# shift_register_MOSFET_1.net
KiCad netlist of a schematic drawn in EAGLE
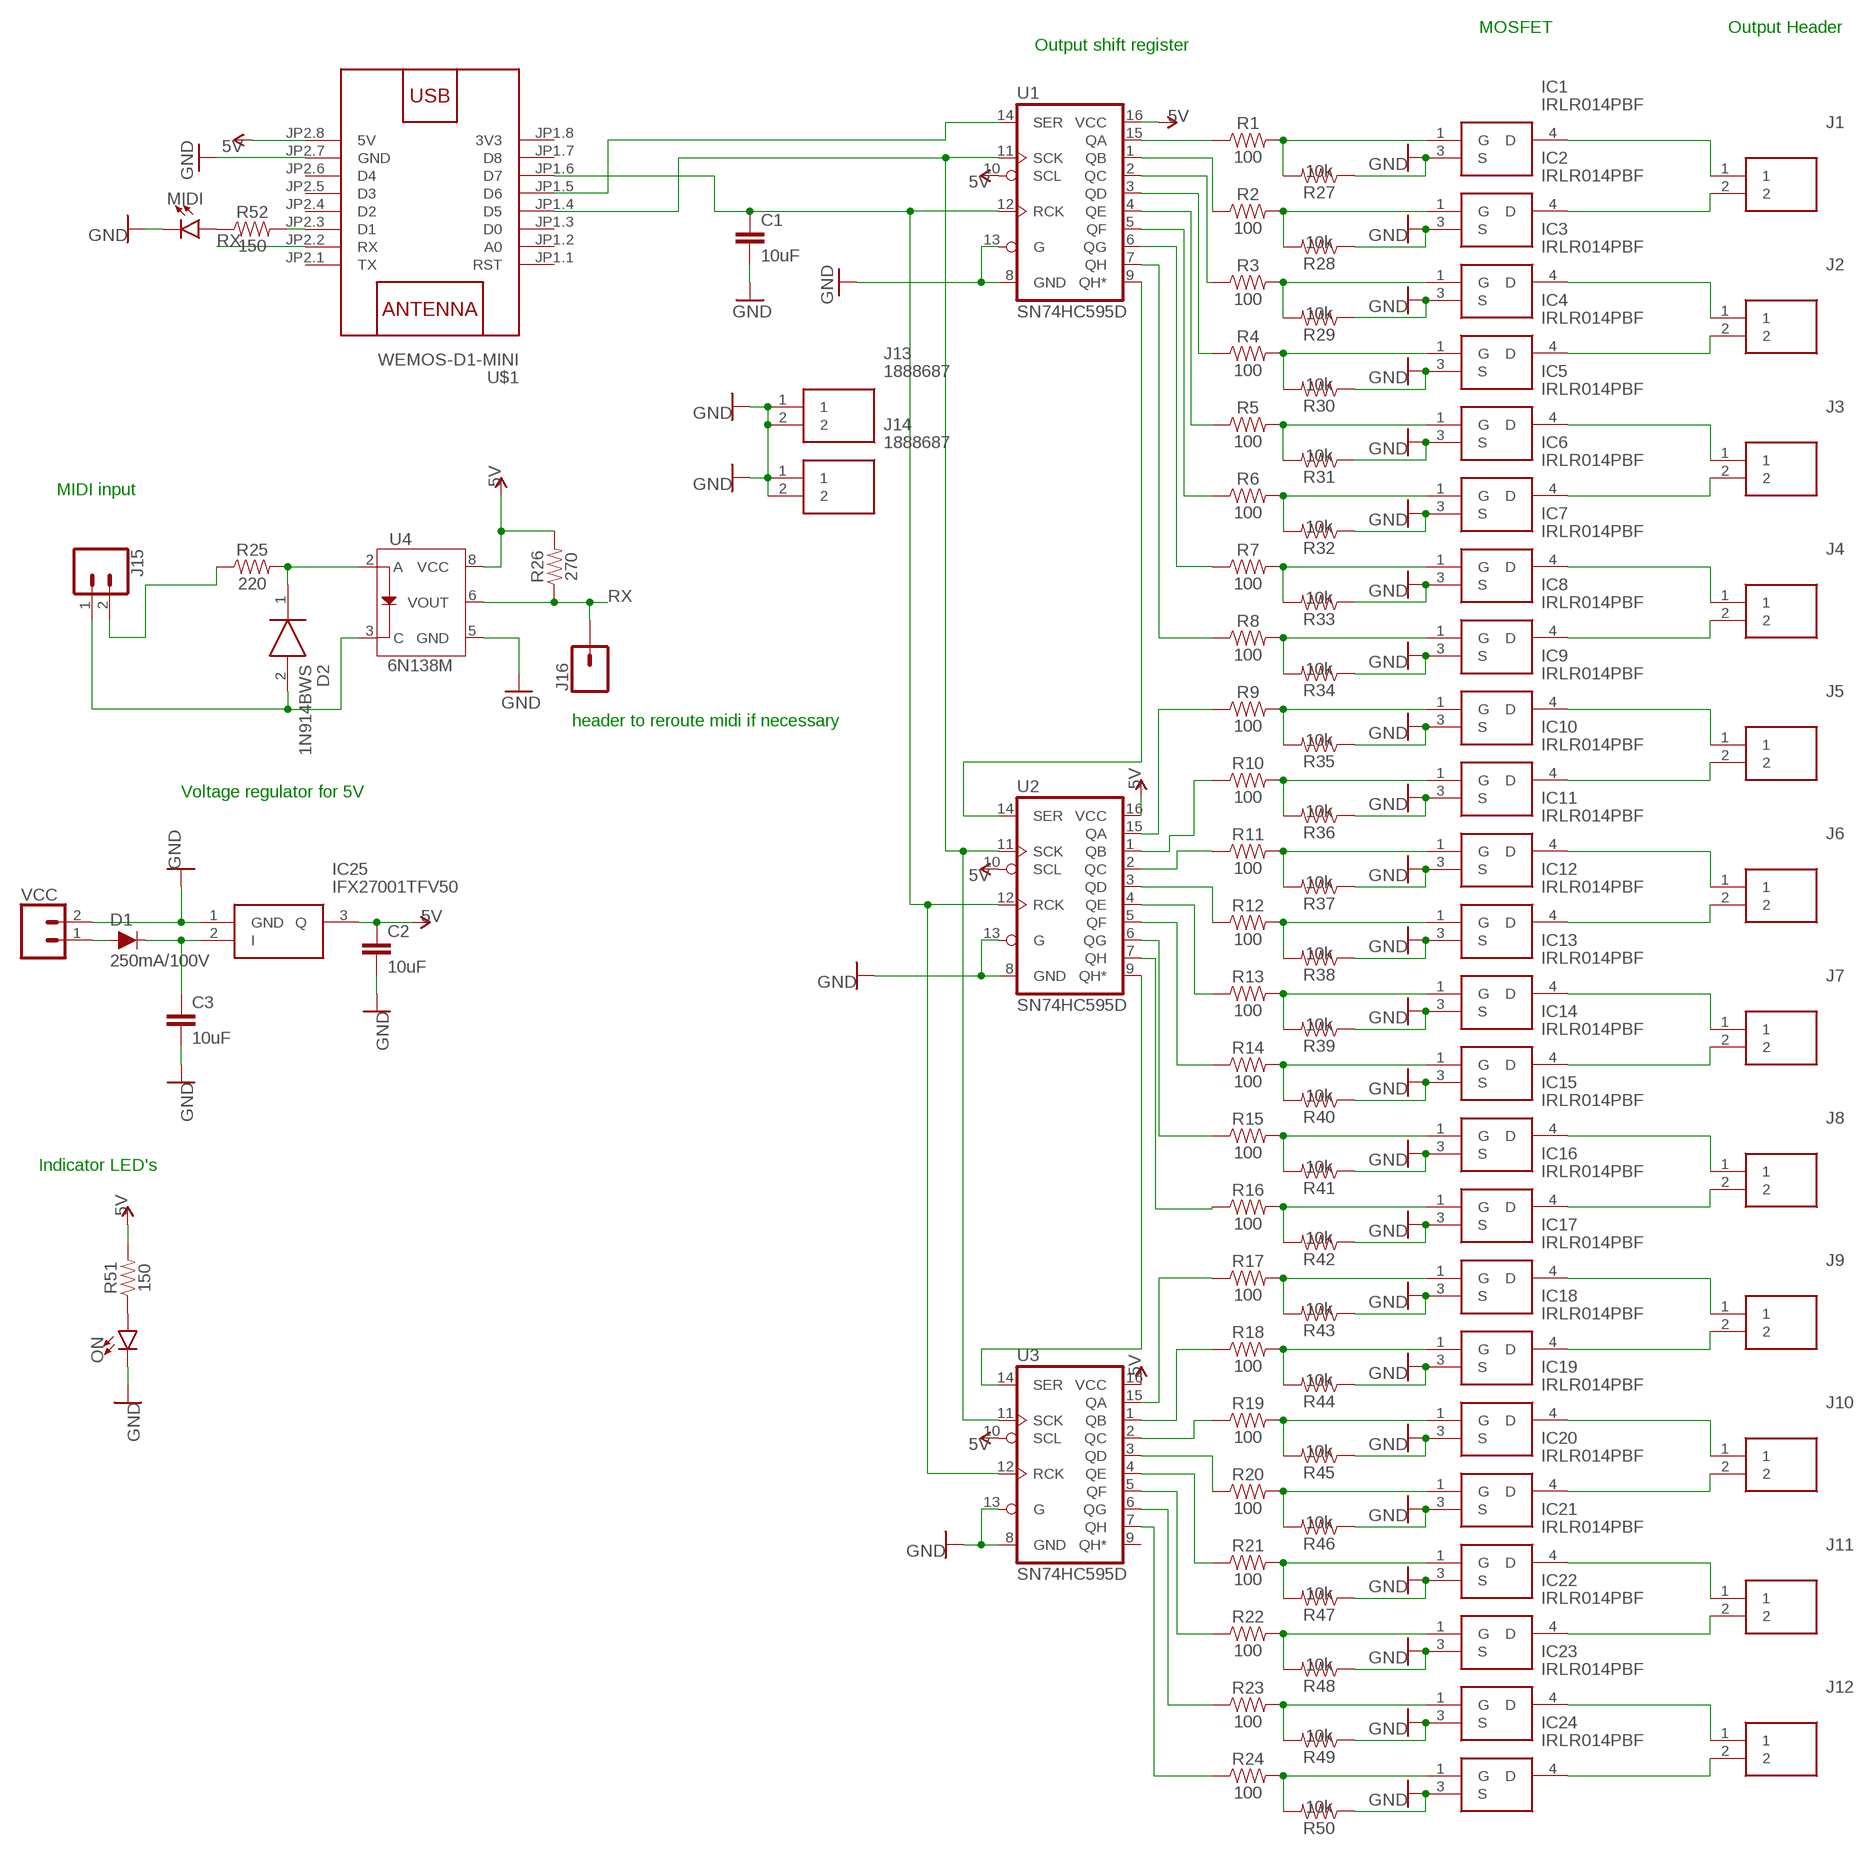
[diagram p0: schematic, sheet 1]

(export (version "E")
  (design (tool "Eeschema 10.0.6"))
  (components
    (comp (ref "C1")
      (value "10uF")
      (footprint "eagle-import:C0805")
      (libsource (lib "eagle-import") (part "C-EUC0805"))
    )
    (comp (ref "C2")
      (value "10uF")
      (footprint "eagle-import:C0805")
      (libsource (lib "eagle-import") (part "C-EUC0805"))
    )
    (comp (ref "C3")
      (value "10uF")
      (footprint "eagle-import:C0805")
      (libsource (lib "eagle-import") (part "C-EUC0805"))
    )
    (comp (ref "D1")
      (value "250mA/100V")
      (footprint "eagle-import:SOD-323")
      (libsource (lib "eagle-import") (part "DIODE-BAS16J"))
    )
    (comp (ref "D2")
      (value "1N914BWS")
      (footprint "eagle-import:SODFL2513X90N")
      (fields (field (name "MOUSER_PART_NUMBER") "512-1N914BWS") (field (name "RS_PART_NUMBER") "8051021P"))
      (libsource (lib "eagle-import") (part "1N914BWS"))
    )
    (comp (ref "IC1")
      (value "IRLR014PBF")
      (footprint "eagle-import:TO228P990X238-3N")
      (fields (field (name "MOUSER_PART_NUMBER") "844-IRLR014PBF") (field (name "RS_PART_NUMBER") "1780908"))
      (libsource (lib "eagle-import") (part "IRLR014PBF"))
    )
    (comp (ref "IC2")
      (value "IRLR014PBF")
      (footprint "eagle-import:TO228P990X238-3N")
      (fields (field (name "MOUSER_PART_NUMBER") "844-IRLR014PBF") (field (name "RS_PART_NUMBER") "1780908"))
      (libsource (lib "eagle-import") (part "IRLR014PBF"))
    )
    (comp (ref "IC3")
      (value "IRLR014PBF")
      (footprint "eagle-import:TO228P990X238-3N")
      (fields (field (name "MOUSER_PART_NUMBER") "844-IRLR014PBF") (field (name "RS_PART_NUMBER") "1780908"))
      (libsource (lib "eagle-import") (part "IRLR014PBF"))
    )
    (comp (ref "IC4")
      (value "IRLR014PBF")
      (footprint "eagle-import:TO228P990X238-3N")
      (fields (field (name "MOUSER_PART_NUMBER") "844-IRLR014PBF") (field (name "RS_PART_NUMBER") "1780908"))
      (libsource (lib "eagle-import") (part "IRLR014PBF"))
    )
    (comp (ref "IC5")
      (value "IRLR014PBF")
      (footprint "eagle-import:TO228P990X238-3N")
      (fields (field (name "MOUSER_PART_NUMBER") "844-IRLR014PBF") (field (name "RS_PART_NUMBER") "1780908"))
      (libsource (lib "eagle-import") (part "IRLR014PBF"))
    )
    (comp (ref "IC6")
      (value "IRLR014PBF")
      (footprint "eagle-import:TO228P990X238-3N")
      (fields (field (name "MOUSER_PART_NUMBER") "844-IRLR014PBF") (field (name "RS_PART_NUMBER") "1780908"))
      (libsource (lib "eagle-import") (part "IRLR014PBF"))
    )
    (comp (ref "IC7")
      (value "IRLR014PBF")
      (footprint "eagle-import:TO228P990X238-3N")
      (fields (field (name "MOUSER_PART_NUMBER") "844-IRLR014PBF") (field (name "RS_PART_NUMBER") "1780908"))
      (libsource (lib "eagle-import") (part "IRLR014PBF"))
    )
    (comp (ref "IC8")
      (value "IRLR014PBF")
      (footprint "eagle-import:TO228P990X238-3N")
      (fields (field (name "MOUSER_PART_NUMBER") "844-IRLR014PBF") (field (name "RS_PART_NUMBER") "1780908"))
      (libsource (lib "eagle-import") (part "IRLR014PBF"))
    )
    (comp (ref "IC9")
      (value "IRLR014PBF")
      (footprint "eagle-import:TO228P990X238-3N")
      (fields (field (name "MOUSER_PART_NUMBER") "844-IRLR014PBF") (field (name "RS_PART_NUMBER") "1780908"))
      (libsource (lib "eagle-import") (part "IRLR014PBF"))
    )
    (comp (ref "IC10")
      (value "IRLR014PBF")
      (footprint "eagle-import:TO228P990X238-3N")
      (fields (field (name "MOUSER_PART_NUMBER") "844-IRLR014PBF") (field (name "RS_PART_NUMBER") "1780908"))
      (libsource (lib "eagle-import") (part "IRLR014PBF"))
    )
    (comp (ref "IC11")
      (value "IRLR014PBF")
      (footprint "eagle-import:TO228P990X238-3N")
      (fields (field (name "MOUSER_PART_NUMBER") "844-IRLR014PBF") (field (name "RS_PART_NUMBER") "1780908"))
      (libsource (lib "eagle-import") (part "IRLR014PBF"))
    )
    (comp (ref "IC12")
      (value "IRLR014PBF")
      (footprint "eagle-import:TO228P990X238-3N")
      (fields (field (name "MOUSER_PART_NUMBER") "844-IRLR014PBF") (field (name "RS_PART_NUMBER") "1780908"))
      (libsource (lib "eagle-import") (part "IRLR014PBF"))
    )
    (comp (ref "IC13")
      (value "IRLR014PBF")
      (footprint "eagle-import:TO228P990X238-3N")
      (fields (field (name "MOUSER_PART_NUMBER") "844-IRLR014PBF") (field (name "RS_PART_NUMBER") "1780908"))
      (libsource (lib "eagle-import") (part "IRLR014PBF"))
    )
    (comp (ref "IC14")
      (value "IRLR014PBF")
      (footprint "eagle-import:TO228P990X238-3N")
      (fields (field (name "MOUSER_PART_NUMBER") "844-IRLR014PBF") (field (name "RS_PART_NUMBER") "1780908"))
      (libsource (lib "eagle-import") (part "IRLR014PBF"))
    )
    (comp (ref "IC15")
      (value "IRLR014PBF")
      (footprint "eagle-import:TO228P990X238-3N")
      (fields (field (name "MOUSER_PART_NUMBER") "844-IRLR014PBF") (field (name "RS_PART_NUMBER") "1780908"))
      (libsource (lib "eagle-import") (part "IRLR014PBF"))
    )
    (comp (ref "IC16")
      (value "IRLR014PBF")
      (footprint "eagle-import:TO228P990X238-3N")
      (fields (field (name "MOUSER_PART_NUMBER") "844-IRLR014PBF") (field (name "RS_PART_NUMBER") "1780908"))
      (libsource (lib "eagle-import") (part "IRLR014PBF"))
    )
    (comp (ref "IC17")
      (value "IRLR014PBF")
      (footprint "eagle-import:TO228P990X238-3N")
      (fields (field (name "MOUSER_PART_NUMBER") "844-IRLR014PBF") (field (name "RS_PART_NUMBER") "1780908"))
      (libsource (lib "eagle-import") (part "IRLR014PBF"))
    )
    (comp (ref "IC18")
      (value "IRLR014PBF")
      (footprint "eagle-import:TO228P990X238-3N")
      (fields (field (name "MOUSER_PART_NUMBER") "844-IRLR014PBF") (field (name "RS_PART_NUMBER") "1780908"))
      (libsource (lib "eagle-import") (part "IRLR014PBF"))
    )
    (comp (ref "IC19")
      (value "IRLR014PBF")
      (footprint "eagle-import:TO228P990X238-3N")
      (fields (field (name "MOUSER_PART_NUMBER") "844-IRLR014PBF") (field (name "RS_PART_NUMBER") "1780908"))
      (libsource (lib "eagle-import") (part "IRLR014PBF"))
    )
    (comp (ref "IC20")
      (value "IRLR014PBF")
      (footprint "eagle-import:TO228P990X238-3N")
      (fields (field (name "MOUSER_PART_NUMBER") "844-IRLR014PBF") (field (name "RS_PART_NUMBER") "1780908"))
      (libsource (lib "eagle-import") (part "IRLR014PBF"))
    )
    (comp (ref "IC21")
      (value "IRLR014PBF")
      (footprint "eagle-import:TO228P990X238-3N")
      (fields (field (name "MOUSER_PART_NUMBER") "844-IRLR014PBF") (field (name "RS_PART_NUMBER") "1780908"))
      (libsource (lib "eagle-import") (part "IRLR014PBF"))
    )
    (comp (ref "IC22")
      (value "IRLR014PBF")
      (footprint "eagle-import:TO228P990X238-3N")
      (fields (field (name "MOUSER_PART_NUMBER") "844-IRLR014PBF") (field (name "RS_PART_NUMBER") "1780908"))
      (libsource (lib "eagle-import") (part "IRLR014PBF"))
    )
    (comp (ref "IC23")
      (value "IRLR014PBF")
      (footprint "eagle-import:TO228P990X238-3N")
      (fields (field (name "MOUSER_PART_NUMBER") "844-IRLR014PBF") (field (name "RS_PART_NUMBER") "1780908"))
      (libsource (lib "eagle-import") (part "IRLR014PBF"))
    )
    (comp (ref "IC24")
      (value "IRLR014PBF")
      (footprint "eagle-import:TO228P990X238-3N")
      (fields (field (name "MOUSER_PART_NUMBER") "844-IRLR014PBF") (field (name "RS_PART_NUMBER") "1780908"))
      (libsource (lib "eagle-import") (part "IRLR014PBF"))
    )
    (comp (ref "IC25")
      (value "IFX27001TFV50")
      (footprint "eagle-import:PG-TO252-3-11")
      (fields (field (name "RS_PART_NUMBER") "1459664"))
      (libsource (lib "eagle-import") (part "IFX27001TFV50"))
    )
    (comp (ref "J1")
      (value "1888687")
      (footprint "eagle-import:SHDR2W90P0X508_1X2_1016X950X15")
      (fields (field (name "MOUSER_PART_NUMBER") "651-1888687") (field (name "RS_PART_NUMBER") "2509972333"))
      (libsource (lib "eagle-import") (part "1888687"))
    )
    (comp (ref "J2")
      (value "1888687")
      (footprint "eagle-import:SHDR2W90P0X508_1X2_1016X950X15")
      (fields (field (name "MOUSER_PART_NUMBER") "651-1888687") (field (name "RS_PART_NUMBER") "2509972333"))
      (libsource (lib "eagle-import") (part "1888687"))
    )
    (comp (ref "J3")
      (value "1888687")
      (footprint "eagle-import:SHDR2W90P0X508_1X2_1016X950X15")
      (fields (field (name "MOUSER_PART_NUMBER") "651-1888687") (field (name "RS_PART_NUMBER") "2509972333"))
      (libsource (lib "eagle-import") (part "1888687"))
    )
    (comp (ref "J4")
      (value "1888687")
      (footprint "eagle-import:SHDR2W90P0X508_1X2_1016X950X15")
      (fields (field (name "MOUSER_PART_NUMBER") "651-1888687") (field (name "RS_PART_NUMBER") "2509972333"))
      (libsource (lib "eagle-import") (part "1888687"))
    )
    (comp (ref "J5")
      (value "1888687")
      (footprint "eagle-import:SHDR2W90P0X508_1X2_1016X950X15")
      (fields (field (name "MOUSER_PART_NUMBER") "651-1888687") (field (name "RS_PART_NUMBER") "2509972333"))
      (libsource (lib "eagle-import") (part "1888687"))
    )
    (comp (ref "J6")
      (value "1888687")
      (footprint "eagle-import:SHDR2W90P0X508_1X2_1016X950X15")
      (fields (field (name "MOUSER_PART_NUMBER") "651-1888687") (field (name "RS_PART_NUMBER") "2509972333"))
      (libsource (lib "eagle-import") (part "1888687"))
    )
    (comp (ref "J7")
      (value "1888687")
      (footprint "eagle-import:SHDR2W90P0X508_1X2_1016X950X15")
      (fields (field (name "MOUSER_PART_NUMBER") "651-1888687") (field (name "RS_PART_NUMBER") "2509972333"))
      (libsource (lib "eagle-import") (part "1888687"))
    )
    (comp (ref "J8")
      (value "1888687")
      (footprint "eagle-import:SHDR2W90P0X508_1X2_1016X950X15")
      (fields (field (name "MOUSER_PART_NUMBER") "651-1888687") (field (name "RS_PART_NUMBER") "2509972333"))
      (libsource (lib "eagle-import") (part "1888687"))
    )
    (comp (ref "J9")
      (value "1888687")
      (footprint "eagle-import:SHDR2W90P0X508_1X2_1016X950X15")
      (fields (field (name "MOUSER_PART_NUMBER") "651-1888687") (field (name "RS_PART_NUMBER") "2509972333"))
      (libsource (lib "eagle-import") (part "1888687"))
    )
    (comp (ref "J10")
      (value "1888687")
      (footprint "eagle-import:SHDR2W90P0X508_1X2_1016X950X15")
      (fields (field (name "MOUSER_PART_NUMBER") "651-1888687") (field (name "RS_PART_NUMBER") "2509972333"))
      (libsource (lib "eagle-import") (part "1888687"))
    )
    (comp (ref "J11")
      (value "1888687")
      (footprint "eagle-import:SHDR2W90P0X508_1X2_1016X950X15")
      (fields (field (name "MOUSER_PART_NUMBER") "651-1888687") (field (name "RS_PART_NUMBER") "2509972333"))
      (libsource (lib "eagle-import") (part "1888687"))
    )
    (comp (ref "J12")
      (value "1888687")
      (footprint "eagle-import:SHDR2W90P0X508_1X2_1016X950X15")
      (fields (field (name "MOUSER_PART_NUMBER") "651-1888687") (field (name "RS_PART_NUMBER") "2509972333"))
      (libsource (lib "eagle-import") (part "1888687"))
    )
    (comp (ref "J13")
      (value "1888687")
      (footprint "eagle-import:SHDR2W90P0X508_1X2_1016X950X15")
      (fields (field (name "MOUSER_PART_NUMBER") "651-1888687") (field (name "RS_PART_NUMBER") "2509972333"))
      (libsource (lib "eagle-import") (part "1888687"))
    )
    (comp (ref "J14")
      (value "1888687")
      (footprint "eagle-import:SHDR2W90P0X508_1X2_1016X950X15")
      (fields (field (name "MOUSER_PART_NUMBER") "651-1888687") (field (name "RS_PART_NUMBER") "2509972333"))
      (libsource (lib "eagle-import") (part "1888687"))
    )
    (comp (ref "J15")
      (value "CONN_02")
      (footprint "eagle-import:1X02")
      (libsource (lib "eagle-import") (part "CONN_02"))
    )
    (comp (ref "J16")
      (value "CONN_01")
      (footprint "eagle-import:1X01")
      (libsource (lib "eagle-import") (part "CONN_01"))
    )
    (comp (ref "MIDI")
      (value "LED3MM")
      (footprint "eagle-import:LED_3MM")
      (libsource (lib "eagle-import") (part "LED3MM"))
    )
    (comp (ref "ON")
      (value "LED3MM")
      (footprint "eagle-import:LED_3MM")
      (libsource (lib "eagle-import") (part "LED3MM"))
    )
    (comp (ref "R1")
      (value "100")
      (footprint "eagle-import:0805")
      (libsource (lib "eagle-import") (part "RESISTOR0805"))
    )
    (comp (ref "R2")
      (value "100")
      (footprint "eagle-import:0805")
      (libsource (lib "eagle-import") (part "RESISTOR0805"))
    )
    (comp (ref "R3")
      (value "100")
      (footprint "eagle-import:0805")
      (libsource (lib "eagle-import") (part "RESISTOR0805"))
    )
    (comp (ref "R4")
      (value "100")
      (footprint "eagle-import:0805")
      (libsource (lib "eagle-import") (part "RESISTOR0805"))
    )
    (comp (ref "R5")
      (value "100")
      (footprint "eagle-import:0805")
      (libsource (lib "eagle-import") (part "RESISTOR0805"))
    )
    (comp (ref "R6")
      (value "100")
      (footprint "eagle-import:0805")
      (libsource (lib "eagle-import") (part "RESISTOR0805"))
    )
    (comp (ref "R7")
      (value "100")
      (footprint "eagle-import:0805")
      (libsource (lib "eagle-import") (part "RESISTOR0805"))
    )
    (comp (ref "R8")
      (value "100")
      (footprint "eagle-import:0805")
      (libsource (lib "eagle-import") (part "RESISTOR0805"))
    )
    (comp (ref "R9")
      (value "100")
      (footprint "eagle-import:0805")
      (libsource (lib "eagle-import") (part "RESISTOR0805"))
    )
    (comp (ref "R10")
      (value "100")
      (footprint "eagle-import:0805")
      (libsource (lib "eagle-import") (part "RESISTOR0805"))
    )
    (comp (ref "R11")
      (value "100")
      (footprint "eagle-import:0805")
      (libsource (lib "eagle-import") (part "RESISTOR0805"))
    )
    (comp (ref "R12")
      (value "100")
      (footprint "eagle-import:0805")
      (libsource (lib "eagle-import") (part "RESISTOR0805"))
    )
    (comp (ref "R13")
      (value "100")
      (footprint "eagle-import:0805")
      (libsource (lib "eagle-import") (part "RESISTOR0805"))
    )
    (comp (ref "R14")
      (value "100")
      (footprint "eagle-import:0805")
      (libsource (lib "eagle-import") (part "RESISTOR0805"))
    )
    (comp (ref "R15")
      (value "100")
      (footprint "eagle-import:0805")
      (libsource (lib "eagle-import") (part "RESISTOR0805"))
    )
    (comp (ref "R16")
      (value "100")
      (footprint "eagle-import:0805")
      (libsource (lib "eagle-import") (part "RESISTOR0805"))
    )
    (comp (ref "R17")
      (value "100")
      (footprint "eagle-import:0805")
      (libsource (lib "eagle-import") (part "RESISTOR0805"))
    )
    (comp (ref "R18")
      (value "100")
      (footprint "eagle-import:0805")
      (libsource (lib "eagle-import") (part "RESISTOR0805"))
    )
    (comp (ref "R19")
      (value "100")
      (footprint "eagle-import:0805")
      (libsource (lib "eagle-import") (part "RESISTOR0805"))
    )
    (comp (ref "R20")
      (value "100")
      (footprint "eagle-import:0805")
      (libsource (lib "eagle-import") (part "RESISTOR0805"))
    )
    (comp (ref "R21")
      (value "100")
      (footprint "eagle-import:0805")
      (libsource (lib "eagle-import") (part "RESISTOR0805"))
    )
    (comp (ref "R22")
      (value "100")
      (footprint "eagle-import:0805")
      (libsource (lib "eagle-import") (part "RESISTOR0805"))
    )
    (comp (ref "R23")
      (value "100")
      (footprint "eagle-import:0805")
      (libsource (lib "eagle-import") (part "RESISTOR0805"))
    )
    (comp (ref "R24")
      (value "100")
      (footprint "eagle-import:0805")
      (libsource (lib "eagle-import") (part "RESISTOR0805"))
    )
    (comp (ref "R25")
      (value "220")
      (footprint "eagle-import:0805")
      (libsource (lib "eagle-import") (part "RESISTOR0805"))
    )
    (comp (ref "R26")
      (value "270")
      (footprint "eagle-import:0805")
      (libsource (lib "eagle-import") (part "RESISTOR0805"))
    )
    (comp (ref "R27")
      (value "10k")
      (footprint "eagle-import:0805")
      (libsource (lib "eagle-import") (part "RESISTOR0805"))
    )
    (comp (ref "R28")
      (value "10k")
      (footprint "eagle-import:0805")
      (libsource (lib "eagle-import") (part "RESISTOR0805"))
    )
    (comp (ref "R29")
      (value "10k")
      (footprint "eagle-import:0805")
      (libsource (lib "eagle-import") (part "RESISTOR0805"))
    )
    (comp (ref "R30")
      (value "10k")
      (footprint "eagle-import:0805")
      (libsource (lib "eagle-import") (part "RESISTOR0805"))
    )
    (comp (ref "R31")
      (value "10k")
      (footprint "eagle-import:0805")
      (libsource (lib "eagle-import") (part "RESISTOR0805"))
    )
    (comp (ref "R32")
      (value "10k")
      (footprint "eagle-import:0805")
      (libsource (lib "eagle-import") (part "RESISTOR0805"))
    )
    (comp (ref "R33")
      (value "10k")
      (footprint "eagle-import:0805")
      (libsource (lib "eagle-import") (part "RESISTOR0805"))
    )
    (comp (ref "R34")
      (value "10k")
      (footprint "eagle-import:0805")
      (libsource (lib "eagle-import") (part "RESISTOR0805"))
    )
    (comp (ref "R35")
      (value "10k")
      (footprint "eagle-import:0805")
      (libsource (lib "eagle-import") (part "RESISTOR0805"))
    )
    (comp (ref "R36")
      (value "10k")
      (footprint "eagle-import:0805")
      (libsource (lib "eagle-import") (part "RESISTOR0805"))
    )
    (comp (ref "R37")
      (value "10k")
      (footprint "eagle-import:0805")
      (libsource (lib "eagle-import") (part "RESISTOR0805"))
    )
    (comp (ref "R38")
      (value "10k")
      (footprint "eagle-import:0805")
      (libsource (lib "eagle-import") (part "RESISTOR0805"))
    )
    (comp (ref "R39")
      (value "10k")
      (footprint "eagle-import:0805")
      (libsource (lib "eagle-import") (part "RESISTOR0805"))
    )
    (comp (ref "R40")
      (value "10k")
      (footprint "eagle-import:0805")
      (libsource (lib "eagle-import") (part "RESISTOR0805"))
    )
    (comp (ref "R41")
      (value "10k")
      (footprint "eagle-import:0805")
      (libsource (lib "eagle-import") (part "RESISTOR0805"))
    )
    (comp (ref "R42")
      (value "10k")
      (footprint "eagle-import:0805")
      (libsource (lib "eagle-import") (part "RESISTOR0805"))
    )
    (comp (ref "R43")
      (value "10k")
      (footprint "eagle-import:0805")
      (libsource (lib "eagle-import") (part "RESISTOR0805"))
    )
    (comp (ref "R44")
      (value "10k")
      (footprint "eagle-import:0805")
      (libsource (lib "eagle-import") (part "RESISTOR0805"))
    )
    (comp (ref "R45")
      (value "10k")
      (footprint "eagle-import:0805")
      (libsource (lib "eagle-import") (part "RESISTOR0805"))
    )
    (comp (ref "R46")
      (value "10k")
      (footprint "eagle-import:0805")
      (libsource (lib "eagle-import") (part "RESISTOR0805"))
    )
    (comp (ref "R47")
      (value "10k")
      (footprint "eagle-import:0805")
      (libsource (lib "eagle-import") (part "RESISTOR0805"))
    )
    (comp (ref "R48")
      (value "10k")
      (footprint "eagle-import:0805")
      (libsource (lib "eagle-import") (part "RESISTOR0805"))
    )
    (comp (ref "R49")
      (value "10k")
      (footprint "eagle-import:0805")
      (libsource (lib "eagle-import") (part "RESISTOR0805"))
    )
    (comp (ref "R50")
      (value "10k")
      (footprint "eagle-import:0805")
      (libsource (lib "eagle-import") (part "RESISTOR0805"))
    )
    (comp (ref "R51")
      (value "150")
      (footprint "eagle-import:0805")
      (libsource (lib "eagle-import") (part "RESISTOR0805"))
    )
    (comp (ref "R52")
      (value "150")
      (footprint "eagle-import:0805")
      (libsource (lib "eagle-import") (part "RESISTOR0805"))
    )
    (comp (ref "U$1")
      (value "WEMOS-D1-MINI")
      (footprint "eagle-import:WEMOS-D1-MINI")
      (libsource (lib "eagle-import") (part "WEMOS-D1-MINI"))
    )
    (comp (ref "U1")
      (value "SN74HC595D")
      (footprint "eagle-import:SO16")
      (libsource (lib "eagle-import") (part "74595DHC"))
    )
    (comp (ref "U2")
      (value "SN74HC595D")
      (footprint "eagle-import:SO16")
      (libsource (lib "eagle-import") (part "74595DHC"))
    )
    (comp (ref "U3")
      (value "SN74HC595D")
      (footprint "eagle-import:SO16")
      (libsource (lib "eagle-import") (part "74595DHC"))
    )
    (comp (ref "U4")
      (value "6N138M")
      (footprint "eagle-import:8-SMD")
      (libsource (lib "eagle-import") (part "OPTO_DARL_6N138S"))
    )
    (comp (ref "VCC")
      (value "CONN_02")
      (footprint "eagle-import:1X02")
      (libsource (lib "eagle-import") (part "CONN_02"))
    )
  )
  (nets
    (net (code "1") (name "/3V3") (class "Default")
      (node (ref "U$1") (pin "JP1.8") (pinfunction "3V3_JP1.8") (pintype "power_in"))
    )
    (net (code "2") (name "/RX") (class "Default")
      (node (ref "J16") (pin "1") (pinfunction "1_1") (pintype "passive"))
      (node (ref "R26") (pin "1") (pinfunction "1_1") (pintype "passive"))
      (node (ref "U$1") (pin "JP2.2") (pinfunction "RX_JP2.2") (pintype "bidirectional"))
      (node (ref "U4") (pin "6") (pinfunction "VOUT_6") (pintype "bidirectional"))
    )
    (net (code "3") (name "5V") (class "Default")
      (node (ref "C2") (pin "1") (pinfunction "1_1") (pintype "passive"))
      (node (ref "IC25") (pin "3") (pinfunction "Q_3") (pintype "bidirectional"))
      (node (ref "R26") (pin "2") (pinfunction "2_2") (pintype "passive"))
      (node (ref "R51") (pin "2") (pinfunction "2_2") (pintype "passive"))
      (node (ref "U$1") (pin "JP2.8") (pinfunction "5V_JP2.8") (pintype "power_in"))
      (node (ref "U1") (pin "10") (pinfunction "SCL_10") (pintype "input"))
      (node (ref "U1") (pin "16") (pinfunction "VCC_16") (pintype "power_in"))
      (node (ref "U2") (pin "10") (pinfunction "SCL_10") (pintype "input"))
      (node (ref "U2") (pin "16") (pinfunction "VCC_16") (pintype "power_in"))
      (node (ref "U3") (pin "10") (pinfunction "SCL_10") (pintype "input"))
      (node (ref "U3") (pin "16") (pinfunction "VCC_16") (pintype "power_in"))
      (node (ref "U4") (pin "8") (pinfunction "VCC_8") (pintype "bidirectional"))
    )
    (net (code "4") (name "GND") (class "Default")
      (node (ref "C1") (pin "2") (pinfunction "2_2") (pintype "passive"))
      (node (ref "C2") (pin "2") (pinfunction "2_2") (pintype "passive"))
      (node (ref "C3") (pin "2") (pinfunction "2_2") (pintype "passive"))
      (node (ref "IC1") (pin "3") (pinfunction "S_3") (pintype "bidirectional"))
      (node (ref "IC10") (pin "3") (pinfunction "S_3") (pintype "bidirectional"))
      (node (ref "IC11") (pin "3") (pinfunction "S_3") (pintype "bidirectional"))
      (node (ref "IC12") (pin "3") (pinfunction "S_3") (pintype "bidirectional"))
      (node (ref "IC13") (pin "3") (pinfunction "S_3") (pintype "bidirectional"))
      (node (ref "IC14") (pin "3") (pinfunction "S_3") (pintype "bidirectional"))
      (node (ref "IC15") (pin "3") (pinfunction "S_3") (pintype "bidirectional"))
      (node (ref "IC16") (pin "3") (pinfunction "S_3") (pintype "bidirectional"))
      (node (ref "IC17") (pin "3") (pinfunction "S_3") (pintype "bidirectional"))
      (node (ref "IC18") (pin "3") (pinfunction "S_3") (pintype "bidirectional"))
      (node (ref "IC19") (pin "3") (pinfunction "S_3") (pintype "bidirectional"))
      (node (ref "IC2") (pin "3") (pinfunction "S_3") (pintype "bidirectional"))
      (node (ref "IC20") (pin "3") (pinfunction "S_3") (pintype "bidirectional"))
      (node (ref "IC21") (pin "3") (pinfunction "S_3") (pintype "bidirectional"))
      (node (ref "IC22") (pin "3") (pinfunction "S_3") (pintype "bidirectional"))
      (node (ref "IC23") (pin "3") (pinfunction "S_3") (pintype "bidirectional"))
      (node (ref "IC24") (pin "3") (pinfunction "S_3") (pintype "bidirectional"))
      (node (ref "IC25") (pin "1") (pinfunction "GND_1") (pintype "bidirectional"))
      (node (ref "IC3") (pin "3") (pinfunction "S_3") (pintype "bidirectional"))
      (node (ref "IC4") (pin "3") (pinfunction "S_3") (pintype "bidirectional"))
      (node (ref "IC5") (pin "3") (pinfunction "S_3") (pintype "bidirectional"))
      (node (ref "IC6") (pin "3") (pinfunction "S_3") (pintype "bidirectional"))
      (node (ref "IC7") (pin "3") (pinfunction "S_3") (pintype "bidirectional"))
      (node (ref "IC8") (pin "3") (pinfunction "S_3") (pintype "bidirectional"))
      (node (ref "IC9") (pin "3") (pinfunction "S_3") (pintype "bidirectional"))
      (node (ref "J13") (pin "1") (pinfunction "1_1") (pintype "bidirectional"))
      (node (ref "J13") (pin "2") (pinfunction "2_2") (pintype "bidirectional"))
      (node (ref "J14") (pin "1") (pinfunction "1_1") (pintype "bidirectional"))
      (node (ref "J14") (pin "2") (pinfunction "2_2") (pintype "bidirectional"))
      (node (ref "MIDI") (pin "K") (pinfunction "C_K") (pintype "passive"))
      (node (ref "ON") (pin "K") (pinfunction "C_K") (pintype "passive"))
      (node (ref "R27") (pin "1") (pinfunction "1_1") (pintype "passive"))
      (node (ref "R28") (pin "1") (pinfunction "1_1") (pintype "passive"))
      (node (ref "R29") (pin "1") (pinfunction "1_1") (pintype "passive"))
      (node (ref "R30") (pin "1") (pinfunction "1_1") (pintype "passive"))
      (node (ref "R31") (pin "1") (pinfunction "1_1") (pintype "passive"))
      (node (ref "R32") (pin "1") (pinfunction "1_1") (pintype "passive"))
      (node (ref "R33") (pin "1") (pinfunction "1_1") (pintype "passive"))
      (node (ref "R34") (pin "1") (pinfunction "1_1") (pintype "passive"))
      (node (ref "R35") (pin "1") (pinfunction "1_1") (pintype "passive"))
      (node (ref "R36") (pin "1") (pinfunction "1_1") (pintype "passive"))
      (node (ref "R37") (pin "1") (pinfunction "1_1") (pintype "passive"))
      (node (ref "R38") (pin "1") (pinfunction "1_1") (pintype "passive"))
      (node (ref "R39") (pin "1") (pinfunction "1_1") (pintype "passive"))
      (node (ref "R40") (pin "1") (pinfunction "1_1") (pintype "passive"))
      (node (ref "R41") (pin "1") (pinfunction "1_1") (pintype "passive"))
      (node (ref "R42") (pin "1") (pinfunction "1_1") (pintype "passive"))
      (node (ref "R43") (pin "1") (pinfunction "1_1") (pintype "passive"))
      (node (ref "R44") (pin "1") (pinfunction "1_1") (pintype "passive"))
      (node (ref "R45") (pin "1") (pinfunction "1_1") (pintype "passive"))
      (node (ref "R46") (pin "1") (pinfunction "1_1") (pintype "passive"))
      (node (ref "R47") (pin "1") (pinfunction "1_1") (pintype "passive"))
      (node (ref "R48") (pin "1") (pinfunction "1_1") (pintype "passive"))
      (node (ref "R49") (pin "1") (pinfunction "1_1") (pintype "passive"))
      (node (ref "R50") (pin "1") (pinfunction "1_1") (pintype "passive"))
      (node (ref "U$1") (pin "JP2.7") (pinfunction "GND_JP2.7") (pintype "power_in"))
      (node (ref "U1") (pin "13") (pinfunction "G_13") (pintype "input"))
      (node (ref "U1") (pin "8") (pinfunction "GND_8") (pintype "power_in"))
      (node (ref "U2") (pin "13") (pinfunction "G_13") (pintype "input"))
      (node (ref "U2") (pin "8") (pinfunction "GND_8") (pintype "power_in"))
      (node (ref "U3") (pin "13") (pinfunction "G_13") (pintype "input"))
      (node (ref "U3") (pin "8") (pinfunction "GND_8") (pintype "power_in"))
      (node (ref "U4") (pin "5") (pinfunction "GND_5") (pintype "bidirectional"))
      (node (ref "VCC") (pin "2") (pinfunction "2_2") (pintype "passive"))
    )
    (net (code "5") (name "Net-(D1-PadA)") (class "Default")
      (node (ref "D1") (pin "A") (pinfunction "A_A") (pintype "passive"))
      (node (ref "VCC") (pin "1") (pinfunction "1_1") (pintype "passive"))
    )
    (net (code "6") (name "Net-(D2-A)") (class "Default")
      (node (ref "D2") (pin "2") (pinfunction "A_2") (pintype "bidirectional"))
      (node (ref "J15") (pin "1") (pinfunction "1_1") (pintype "passive"))
      (node (ref "U4") (pin "3") (pinfunction "C_3") (pintype "bidirectional"))
    )
    (net (code "7") (name "Net-(D2-K)") (class "Default")
      (node (ref "D2") (pin "1") (pinfunction "K_1") (pintype "bidirectional"))
      (node (ref "R25") (pin "2") (pinfunction "2_2") (pintype "passive"))
      (node (ref "U4") (pin "2") (pinfunction "A_2") (pintype "bidirectional"))
    )
    (net (code "8") (name "Net-(IC1-D)") (class "Default")
      (node (ref "IC1") (pin "4") (pinfunction "D_4") (pintype "bidirectional"))
      (node (ref "J1") (pin "1") (pinfunction "1_1") (pintype "bidirectional"))
    )
    (net (code "9") (name "Net-(IC1-G)") (class "Default")
      (node (ref "IC1") (pin "1") (pinfunction "G_1") (pintype "bidirectional"))
      (node (ref "R1") (pin "2") (pinfunction "2_2") (pintype "passive"))
      (node (ref "R27") (pin "2") (pinfunction "2_2") (pintype "passive"))
    )
    (net (code "10") (name "Net-(IC2-D)") (class "Default")
      (node (ref "IC2") (pin "4") (pinfunction "D_4") (pintype "bidirectional"))
      (node (ref "J1") (pin "2") (pinfunction "2_2") (pintype "bidirectional"))
    )
    (net (code "11") (name "Net-(IC2-G)") (class "Default")
      (node (ref "IC2") (pin "1") (pinfunction "G_1") (pintype "bidirectional"))
      (node (ref "R2") (pin "2") (pinfunction "2_2") (pintype "passive"))
      (node (ref "R28") (pin "2") (pinfunction "2_2") (pintype "passive"))
    )
    (net (code "12") (name "Net-(IC3-D)") (class "Default")
      (node (ref "IC3") (pin "4") (pinfunction "D_4") (pintype "bidirectional"))
      (node (ref "J2") (pin "1") (pinfunction "1_1") (pintype "bidirectional"))
    )
    (net (code "13") (name "Net-(IC3-G)") (class "Default")
      (node (ref "IC3") (pin "1") (pinfunction "G_1") (pintype "bidirectional"))
      (node (ref "R29") (pin "2") (pinfunction "2_2") (pintype "passive"))
      (node (ref "R3") (pin "2") (pinfunction "2_2") (pintype "passive"))
    )
    (net (code "14") (name "Net-(IC4-D)") (class "Default")
      (node (ref "IC4") (pin "4") (pinfunction "D_4") (pintype "bidirectional"))
      (node (ref "J2") (pin "2") (pinfunction "2_2") (pintype "bidirectional"))
    )
    (net (code "15") (name "Net-(IC4-G)") (class "Default")
      (node (ref "IC4") (pin "1") (pinfunction "G_1") (pintype "bidirectional"))
      (node (ref "R30") (pin "2") (pinfunction "2_2") (pintype "passive"))
      (node (ref "R4") (pin "2") (pinfunction "2_2") (pintype "passive"))
    )
    (net (code "16") (name "Net-(IC5-D)") (class "Default")
      (node (ref "IC5") (pin "4") (pinfunction "D_4") (pintype "bidirectional"))
      (node (ref "J3") (pin "1") (pinfunction "1_1") (pintype "bidirectional"))
    )
    (net (code "17") (name "Net-(IC5-G)") (class "Default")
      (node (ref "IC5") (pin "1") (pinfunction "G_1") (pintype "bidirectional"))
      (node (ref "R31") (pin "2") (pinfunction "2_2") (pintype "passive"))
      (node (ref "R5") (pin "2") (pinfunction "2_2") (pintype "passive"))
    )
    (net (code "18") (name "Net-(IC6-D)") (class "Default")
      (node (ref "IC6") (pin "4") (pinfunction "D_4") (pintype "bidirectional"))
      (node (ref "J3") (pin "2") (pinfunction "2_2") (pintype "bidirectional"))
    )
    (net (code "19") (name "Net-(IC6-G)") (class "Default")
      (node (ref "IC6") (pin "1") (pinfunction "G_1") (pintype "bidirectional"))
      (node (ref "R32") (pin "2") (pinfunction "2_2") (pintype "passive"))
      (node (ref "R6") (pin "2") (pinfunction "2_2") (pintype "passive"))
    )
    (net (code "20") (name "Net-(IC7-D)") (class "Default")
      (node (ref "IC7") (pin "4") (pinfunction "D_4") (pintype "bidirectional"))
      (node (ref "J4") (pin "1") (pinfunction "1_1") (pintype "bidirectional"))
    )
    (net (code "21") (name "Net-(IC7-G)") (class "Default")
      (node (ref "IC7") (pin "1") (pinfunction "G_1") (pintype "bidirectional"))
      (node (ref "R33") (pin "2") (pinfunction "2_2") (pintype "passive"))
      (node (ref "R7") (pin "2") (pinfunction "2_2") (pintype "passive"))
    )
    (net (code "22") (name "Net-(IC8-D)") (class "Default")
      (node (ref "IC8") (pin "4") (pinfunction "D_4") (pintype "bidirectional"))
      (node (ref "J4") (pin "2") (pinfunction "2_2") (pintype "bidirectional"))
    )
    (net (code "23") (name "Net-(IC8-G)") (class "Default")
      (node (ref "IC8") (pin "1") (pinfunction "G_1") (pintype "bidirectional"))
      (node (ref "R34") (pin "2") (pinfunction "2_2") (pintype "passive"))
      (node (ref "R8") (pin "2") (pinfunction "2_2") (pintype "passive"))
    )
    (net (code "24") (name "Net-(IC9-D)") (class "Default")
      (node (ref "IC9") (pin "4") (pinfunction "D_4") (pintype "bidirectional"))
      (node (ref "J5") (pin "1") (pinfunction "1_1") (pintype "bidirectional"))
    )
    (net (code "25") (name "Net-(IC9-G)") (class "Default")
      (node (ref "IC9") (pin "1") (pinfunction "G_1") (pintype "bidirectional"))
      (node (ref "R35") (pin "2") (pinfunction "2_2") (pintype "passive"))
      (node (ref "R9") (pin "2") (pinfunction "2_2") (pintype "passive"))
    )
    (net (code "26") (name "Net-(IC10-D)") (class "Default")
      (node (ref "IC10") (pin "4") (pinfunction "D_4") (pintype "bidirectional"))
      (node (ref "J5") (pin "2") (pinfunction "2_2") (pintype "bidirectional"))
    )
    (net (code "27") (name "Net-(IC10-G)") (class "Default")
      (node (ref "IC10") (pin "1") (pinfunction "G_1") (pintype "bidirectional"))
      (node (ref "R10") (pin "2") (pinfunction "2_2") (pintype "passive"))
      (node (ref "R36") (pin "2") (pinfunction "2_2") (pintype "passive"))
    )
    (net (code "28") (name "Net-(IC11-D)") (class "Default")
      (node (ref "IC11") (pin "4") (pinfunction "D_4") (pintype "bidirectional"))
      (node (ref "J6") (pin "1") (pinfunction "1_1") (pintype "bidirectional"))
    )
    (net (code "29") (name "Net-(IC11-G)") (class "Default")
      (node (ref "IC11") (pin "1") (pinfunction "G_1") (pintype "bidirectional"))
      (node (ref "R11") (pin "2") (pinfunction "2_2") (pintype "passive"))
      (node (ref "R37") (pin "2") (pinfunction "2_2") (pintype "passive"))
    )
    (net (code "30") (name "Net-(IC12-D)") (class "Default")
      (node (ref "IC12") (pin "4") (pinfunction "D_4") (pintype "bidirectional"))
      (node (ref "J6") (pin "2") (pinfunction "2_2") (pintype "bidirectional"))
    )
    (net (code "31") (name "Net-(IC12-G)") (class "Default")
      (node (ref "IC12") (pin "1") (pinfunction "G_1") (pintype "bidirectional"))
      (node (ref "R12") (pin "2") (pinfunction "2_2") (pintype "passive"))
      (node (ref "R38") (pin "2") (pinfunction "2_2") (pintype "passive"))
    )
    (net (code "32") (name "Net-(IC13-D)") (class "Default")
      (node (ref "IC13") (pin "4") (pinfunction "D_4") (pintype "bidirectional"))
      (node (ref "J7") (pin "1") (pinfunction "1_1") (pintype "bidirectional"))
    )
    (net (code "33") (name "Net-(IC13-G)") (class "Default")
      (node (ref "IC13") (pin "1") (pinfunction "G_1") (pintype "bidirectional"))
      (node (ref "R13") (pin "2") (pinfunction "2_2") (pintype "passive"))
      (node (ref "R39") (pin "2") (pinfunction "2_2") (pintype "passive"))
    )
    (net (code "34") (name "Net-(IC14-D)") (class "Default")
      (node (ref "IC14") (pin "4") (pinfunction "D_4") (pintype "bidirectional"))
      (node (ref "J7") (pin "2") (pinfunction "2_2") (pintype "bidirectional"))
    )
    (net (code "35") (name "Net-(IC14-G)") (class "Default")
      (node (ref "IC14") (pin "1") (pinfunction "G_1") (pintype "bidirectional"))
      (node (ref "R14") (pin "2") (pinfunction "2_2") (pintype "passive"))
      (node (ref "R40") (pin "2") (pinfunction "2_2") (pintype "passive"))
    )
    (net (code "36") (name "Net-(IC15-D)") (class "Default")
      (node (ref "IC15") (pin "4") (pinfunction "D_4") (pintype "bidirectional"))
      (node (ref "J8") (pin "1") (pinfunction "1_1") (pintype "bidirectional"))
    )
    (net (code "37") (name "Net-(IC15-G)") (class "Default")
      (node (ref "IC15") (pin "1") (pinfunction "G_1") (pintype "bidirectional"))
      (node (ref "R15") (pin "2") (pinfunction "2_2") (pintype "passive"))
      (node (ref "R41") (pin "2") (pinfunction "2_2") (pintype "passive"))
    )
    (net (code "38") (name "Net-(IC16-D)") (class "Default")
      (node (ref "IC16") (pin "4") (pinfunction "D_4") (pintype "bidirectional"))
      (node (ref "J8") (pin "2") (pinfunction "2_2") (pintype "bidirectional"))
    )
    (net (code "39") (name "Net-(IC16-G)") (class "Default")
      (node (ref "IC16") (pin "1") (pinfunction "G_1") (pintype "bidirectional"))
      (node (ref "R16") (pin "2") (pinfunction "2_2") (pintype "passive"))
      (node (ref "R42") (pin "2") (pinfunction "2_2") (pintype "passive"))
    )
    (net (code "40") (name "Net-(IC17-D)") (class "Default")
      (node (ref "IC17") (pin "4") (pinfunction "D_4") (pintype "bidirectional"))
      (node (ref "J9") (pin "1") (pinfunction "1_1") (pintype "bidirectional"))
    )
    (net (code "41") (name "Net-(IC17-G)") (class "Default")
      (node (ref "IC17") (pin "1") (pinfunction "G_1") (pintype "bidirectional"))
      (node (ref "R17") (pin "2") (pinfunction "2_2") (pintype "passive"))
      (node (ref "R43") (pin "2") (pinfunction "2_2") (pintype "passive"))
    )
    (net (code "42") (name "Net-(IC18-D)") (class "Default")
      (node (ref "IC18") (pin "4") (pinfunction "D_4") (pintype "bidirectional"))
      (node (ref "J9") (pin "2") (pinfunction "2_2") (pintype "bidirectional"))
    )
    (net (code "43") (name "Net-(IC18-G)") (class "Default")
      (node (ref "IC18") (pin "1") (pinfunction "G_1") (pintype "bidirectional"))
      (node (ref "R18") (pin "2") (pinfunction "2_2") (pintype "passive"))
      (node (ref "R44") (pin "2") (pinfunction "2_2") (pintype "passive"))
    )
    (net (code "44") (name "Net-(IC19-D)") (class "Default")
      (node (ref "IC19") (pin "4") (pinfunction "D_4") (pintype "bidirectional"))
      (node (ref "J10") (pin "1") (pinfunction "1_1") (pintype "bidirectional"))
    )
    (net (code "45") (name "Net-(IC19-G)") (class "Default")
      (node (ref "IC19") (pin "1") (pinfunction "G_1") (pintype "bidirectional"))
      (node (ref "R19") (pin "2") (pinfunction "2_2") (pintype "passive"))
      (node (ref "R45") (pin "2") (pinfunction "2_2") (pintype "passive"))
    )
    (net (code "46") (name "Net-(IC20-D)") (class "Default")
      (node (ref "IC20") (pin "4") (pinfunction "D_4") (pintype "bidirectional"))
      (node (ref "J10") (pin "2") (pinfunction "2_2") (pintype "bidirectional"))
    )
    (net (code "47") (name "Net-(IC20-G)") (class "Default")
      (node (ref "IC20") (pin "1") (pinfunction "G_1") (pintype "bidirectional"))
      (node (ref "R20") (pin "2") (pinfunction "2_2") (pintype "passive"))
      (node (ref "R46") (pin "2") (pinfunction "2_2") (pintype "passive"))
    )
    (net (code "48") (name "Net-(IC21-D)") (class "Default")
      (node (ref "IC21") (pin "4") (pinfunction "D_4") (pintype "bidirectional"))
      (node (ref "J11") (pin "1") (pinfunction "1_1") (pintype "bidirectional"))
    )
    (net (code "49") (name "Net-(IC21-G)") (class "Default")
      (node (ref "IC21") (pin "1") (pinfunction "G_1") (pintype "bidirectional"))
      (node (ref "R21") (pin "2") (pinfunction "2_2") (pintype "passive"))
      (node (ref "R47") (pin "2") (pinfunction "2_2") (pintype "passive"))
    )
    (net (code "50") (name "Net-(IC22-D)") (class "Default")
      (node (ref "IC22") (pin "4") (pinfunction "D_4") (pintype "bidirectional"))
      (node (ref "J11") (pin "2") (pinfunction "2_2") (pintype "bidirectional"))
    )
    (net (code "51") (name "Net-(IC22-G)") (class "Default")
      (node (ref "IC22") (pin "1") (pinfunction "G_1") (pintype "bidirectional"))
      (node (ref "R22") (pin "2") (pinfunction "2_2") (pintype "passive"))
      (node (ref "R48") (pin "2") (pinfunction "2_2") (pintype "passive"))
    )
    (net (code "52") (name "Net-(IC23-D)") (class "Default")
      (node (ref "IC23") (pin "4") (pinfunction "D_4") (pintype "bidirectional"))
      (node (ref "J12") (pin "1") (pinfunction "1_1") (pintype "bidirectional"))
    )
    (net (code "53") (name "Net-(IC23-G)") (class "Default")
      (node (ref "IC23") (pin "1") (pinfunction "G_1") (pintype "bidirectional"))
      (node (ref "R23") (pin "2") (pinfunction "2_2") (pintype "passive"))
      (node (ref "R49") (pin "2") (pinfunction "2_2") (pintype "passive"))
    )
    (net (code "54") (name "Net-(IC24-D)") (class "Default")
      (node (ref "IC24") (pin "4") (pinfunction "D_4") (pintype "bidirectional"))
      (node (ref "J12") (pin "2") (pinfunction "2_2") (pintype "bidirectional"))
    )
    (net (code "55") (name "Net-(IC24-G)") (class "Default")
      (node (ref "IC24") (pin "1") (pinfunction "G_1") (pintype "bidirectional"))
      (node (ref "R24") (pin "2") (pinfunction "2_2") (pintype "passive"))
      (node (ref "R50") (pin "2") (pinfunction "2_2") (pintype "passive"))
    )
    (net (code "56") (name "Net-(IC25-I)") (class "Default")
      (node (ref "C3") (pin "1") (pinfunction "1_1") (pintype "passive"))
      (node (ref "D1") (pin "C") (pinfunction "C_C") (pintype "passive"))
      (node (ref "IC25") (pin "2") (pinfunction "I_2") (pintype "bidirectional"))
    )
    (net (code "57") (name "Net-(J15-Pad2)") (class "Default")
      (node (ref "J15") (pin "2") (pinfunction "2_2") (pintype "passive"))
      (node (ref "R25") (pin "1") (pinfunction "1_1") (pintype "passive"))
    )
    (net (code "58") (name "Net-(MIDI-PadA)") (class "Default")
      (node (ref "MIDI") (pin "A") (pinfunction "A_A") (pintype "passive"))
      (node (ref "R52") (pin "1") (pinfunction "1_1") (pintype "passive"))
    )
    (net (code "59") (name "Net-(ON-PadA)") (class "Default")
      (node (ref "ON") (pin "A") (pinfunction "A_A") (pintype "passive"))
      (node (ref "R51") (pin "1") (pinfunction "1_1") (pintype "passive"))
    )
    (net (code "60") (name "Net-(U$1-D1)") (class "Default")
      (node (ref "R52") (pin "2") (pinfunction "2_2") (pintype "passive"))
      (node (ref "U$1") (pin "JP2.3") (pinfunction "D1_JP2.3") (pintype "bidirectional"))
    )
    (net (code "61") (name "Net-(U$1-D5)") (class "Default")
      (node (ref "U$1") (pin "JP1.4") (pinfunction "D5_JP1.4") (pintype "bidirectional"))
      (node (ref "U1") (pin "11") (pinfunction "SCK_11") (pintype "input"))
      (node (ref "U2") (pin "11") (pinfunction "SCK_11") (pintype "input"))
      (node (ref "U3") (pin "11") (pinfunction "SCK_11") (pintype "input"))
    )
    (net (code "62") (name "Net-(U$1-D6)") (class "Default")
      (node (ref "U$1") (pin "JP1.5") (pinfunction "D6_JP1.5") (pintype "bidirectional"))
      (node (ref "U1") (pin "14") (pinfunction "SER_14") (pintype "input"))
    )
    (net (code "63") (name "Net-(U$1-D7)") (class "Default")
      (node (ref "C1") (pin "1") (pinfunction "1_1") (pintype "passive"))
      (node (ref "U$1") (pin "JP1.6") (pinfunction "D7_JP1.6") (pintype "bidirectional"))
      (node (ref "U1") (pin "12") (pinfunction "RCK_12") (pintype "input"))
      (node (ref "U2") (pin "12") (pinfunction "RCK_12") (pintype "input"))
      (node (ref "U3") (pin "12") (pinfunction "RCK_12") (pintype "input"))
    )
    (net (code "64") (name "Net-(U1-QA)") (class "Default")
      (node (ref "R1") (pin "1") (pinfunction "1_1") (pintype "passive"))
      (node (ref "U1") (pin "15") (pinfunction "QA_15") (pintype "tri_state"))
    )
    (net (code "65") (name "Net-(U1-QB)") (class "Default")
      (node (ref "R2") (pin "1") (pinfunction "1_1") (pintype "passive"))
      (node (ref "U1") (pin "1") (pinfunction "QB_1") (pintype "tri_state"))
    )
    (net (code "66") (name "Net-(U1-QC)") (class "Default")
      (node (ref "R3") (pin "1") (pinfunction "1_1") (pintype "passive"))
      (node (ref "U1") (pin "2") (pinfunction "QC_2") (pintype "tri_state"))
    )
    (net (code "67") (name "Net-(U1-QD)") (class "Default")
      (node (ref "R4") (pin "1") (pinfunction "1_1") (pintype "passive"))
      (node (ref "U1") (pin "3") (pinfunction "QD_3") (pintype "tri_state"))
    )
    (net (code "68") (name "Net-(U1-QE)") (class "Default")
      (node (ref "R5") (pin "1") (pinfunction "1_1") (pintype "passive"))
      (node (ref "U1") (pin "4") (pinfunction "QE_4") (pintype "tri_state"))
    )
    (net (code "69") (name "Net-(U1-QF)") (class "Default")
      (node (ref "R6") (pin "1") (pinfunction "1_1") (pintype "passive"))
      (node (ref "U1") (pin "5") (pinfunction "QF_5") (pintype "tri_state"))
    )
    (net (code "70") (name "Net-(U1-QG)") (class "Default")
      (node (ref "R7") (pin "1") (pinfunction "1_1") (pintype "passive"))
      (node (ref "U1") (pin "6") (pinfunction "QG_6") (pintype "tri_state"))
    )
    (net (code "71") (name "Net-(U1-QH)") (class "Default")
      (node (ref "R8") (pin "1") (pinfunction "1_1") (pintype "passive"))
      (node (ref "U1") (pin "7") (pinfunction "QH_7") (pintype "tri_state"))
    )
    (net (code "72") (name "Net-(U1-QH*)") (class "Default")
      (node (ref "U1") (pin "9") (pinfunction "QH*_9") (pintype "tri_state"))
      (node (ref "U2") (pin "14") (pinfunction "SER_14") (pintype "input"))
    )
    (net (code "73") (name "Net-(U2-QA)") (class "Default")
      (node (ref "R9") (pin "1") (pinfunction "1_1") (pintype "passive"))
      (node (ref "U2") (pin "15") (pinfunction "QA_15") (pintype "tri_state"))
    )
    (net (code "74") (name "Net-(U2-QB)") (class "Default")
      (node (ref "R10") (pin "1") (pinfunction "1_1") (pintype "passive"))
      (node (ref "U2") (pin "1") (pinfunction "QB_1") (pintype "tri_state"))
    )
    (net (code "75") (name "Net-(U2-QC)") (class "Default")
      (node (ref "R11") (pin "1") (pinfunction "1_1") (pintype "passive"))
      (node (ref "U2") (pin "2") (pinfunction "QC_2") (pintype "tri_state"))
    )
    (net (code "76") (name "Net-(U2-QD)") (class "Default")
      (node (ref "R12") (pin "1") (pinfunction "1_1") (pintype "passive"))
      (node (ref "U2") (pin "3") (pinfunction "QD_3") (pintype "tri_state"))
    )
    (net (code "77") (name "Net-(U2-QE)") (class "Default")
      (node (ref "R13") (pin "1") (pinfunction "1_1") (pintype "passive"))
      (node (ref "U2") (pin "4") (pinfunction "QE_4") (pintype "tri_state"))
    )
    (net (code "78") (name "Net-(U2-QF)") (class "Default")
      (node (ref "R14") (pin "1") (pinfunction "1_1") (pintype "passive"))
      (node (ref "U2") (pin "5") (pinfunction "QF_5") (pintype "tri_state"))
    )
    (net (code "79") (name "Net-(U2-QG)") (class "Default")
      (node (ref "R15") (pin "1") (pinfunction "1_1") (pintype "passive"))
      (node (ref "U2") (pin "6") (pinfunction "QG_6") (pintype "tri_state"))
    )
    (net (code "80") (name "Net-(U2-QH)") (class "Default")
      (node (ref "R16") (pin "1") (pinfunction "1_1") (pintype "passive"))
      (node (ref "U2") (pin "7") (pinfunction "QH_7") (pintype "tri_state"))
    )
    (net (code "81") (name "Net-(U2-QH*)") (class "Default")
      (node (ref "U2") (pin "9") (pinfunction "QH*_9") (pintype "tri_state"))
      (node (ref "U3") (pin "14") (pinfunction "SER_14") (pintype "input"))
    )
    (net (code "82") (name "Net-(U3-QA)") (class "Default")
      (node (ref "R17") (pin "1") (pinfunction "1_1") (pintype "passive"))
      (node (ref "U3") (pin "15") (pinfunction "QA_15") (pintype "tri_state"))
    )
    (net (code "83") (name "Net-(U3-QB)") (class "Default")
      (node (ref "R18") (pin "1") (pinfunction "1_1") (pintype "passive"))
      (node (ref "U3") (pin "1") (pinfunction "QB_1") (pintype "tri_state"))
    )
    (net (code "84") (name "Net-(U3-QC)") (class "Default")
      (node (ref "R19") (pin "1") (pinfunction "1_1") (pintype "passive"))
      (node (ref "U3") (pin "2") (pinfunction "QC_2") (pintype "tri_state"))
    )
    (net (code "85") (name "Net-(U3-QD)") (class "Default")
      (node (ref "R20") (pin "1") (pinfunction "1_1") (pintype "passive"))
      (node (ref "U3") (pin "3") (pinfunction "QD_3") (pintype "tri_state"))
    )
    (net (code "86") (name "Net-(U3-QE)") (class "Default")
      (node (ref "R21") (pin "1") (pinfunction "1_1") (pintype "passive"))
      (node (ref "U3") (pin "4") (pinfunction "QE_4") (pintype "tri_state"))
    )
    (net (code "87") (name "Net-(U3-QF)") (class "Default")
      (node (ref "R22") (pin "1") (pinfunction "1_1") (pintype "passive"))
      (node (ref "U3") (pin "5") (pinfunction "QF_5") (pintype "tri_state"))
    )
    (net (code "88") (name "Net-(U3-QG)") (class "Default")
      (node (ref "R23") (pin "1") (pinfunction "1_1") (pintype "passive"))
      (node (ref "U3") (pin "6") (pinfunction "QG_6") (pintype "tri_state"))
    )
    (net (code "89") (name "Net-(U3-QH)") (class "Default")
      (node (ref "R24") (pin "1") (pinfunction "1_1") (pintype "passive"))
      (node (ref "U3") (pin "7") (pinfunction "QH_7") (pintype "tri_state"))
    )
    (net (code "90") (name "unconnected-(U$1-A0-PadJP1.2)") (class "Default")
      (node (ref "U$1") (pin "JP1.2") (pinfunction "A0_JP1.2") (pintype "bidirectional"))
    )
    (net (code "91") (name "unconnected-(U$1-D0-PadJP1.3)") (class "Default")
      (node (ref "U$1") (pin "JP1.3") (pinfunction "D0_JP1.3") (pintype "bidirectional"))
    )
    (net (code "92") (name "unconnected-(U$1-D2-PadJP2.4)") (class "Default")
      (node (ref "U$1") (pin "JP2.4") (pinfunction "D2_JP2.4") (pintype "bidirectional"))
    )
    (net (code "93") (name "unconnected-(U$1-D3-PadJP2.5)") (class "Default")
      (node (ref "U$1") (pin "JP2.5") (pinfunction "D3_JP2.5") (pintype "bidirectional"))
    )
    (net (code "94") (name "unconnected-(U$1-D4-PadJP2.6)") (class "Default")
      (node (ref "U$1") (pin "JP2.6") (pinfunction "D4_JP2.6") (pintype "bidirectional"))
    )
    (net (code "95") (name "unconnected-(U$1-D8-PadJP1.7)") (class "Default")
      (node (ref "U$1") (pin "JP1.7") (pinfunction "D8_JP1.7") (pintype "bidirectional"))
    )
    (net (code "96") (name "unconnected-(U$1-RST-PadJP1.1)") (class "Default")
      (node (ref "U$1") (pin "JP1.1") (pinfunction "RST_JP1.1") (pintype "bidirectional"))
    )
    (net (code "97") (name "unconnected-(U$1-TX-PadJP2.1)") (class "Default")
      (node (ref "U$1") (pin "JP2.1") (pinfunction "TX_JP2.1") (pintype "bidirectional"))
    )
    (net (code "98") (name "unconnected-(U3-QH*-Pad9)") (class "Default")
      (node (ref "U3") (pin "9") (pinfunction "QH*_9") (pintype "tri_state"))
    )
  )
)
